# interconnexions.net
KiCad netlist of a schematic drawn in EAGLE
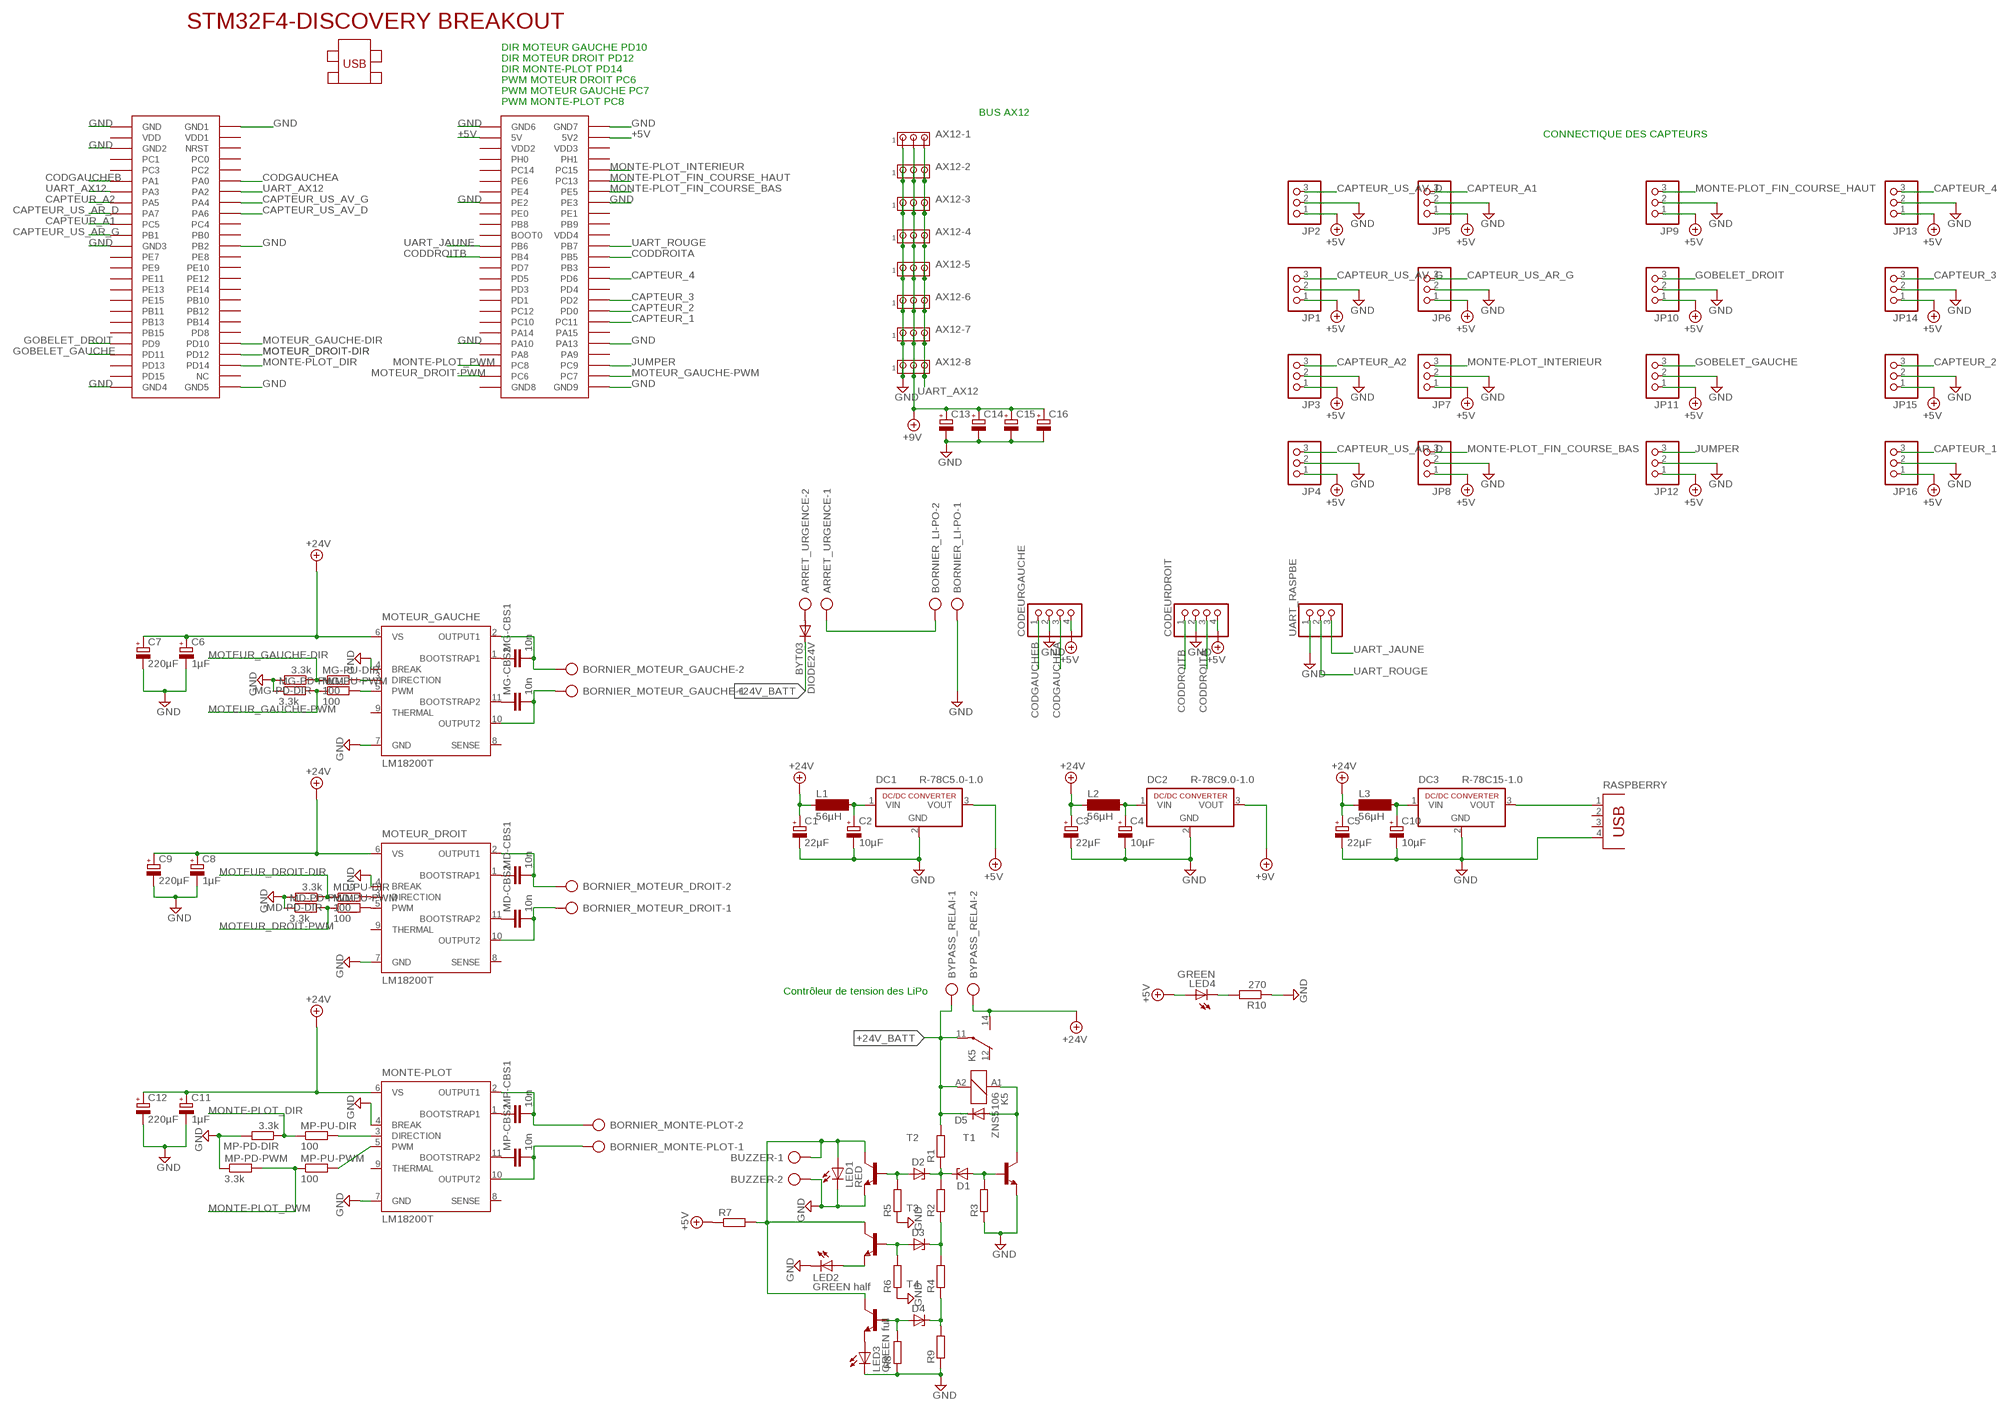
[diagram p0: schematic, sheet 1]

(export (version "E")
  (design (tool "Eeschema 10.0.6"))
  (components
    (comp (ref "ARRET_URGENCE")
      (value "AK300/2")
      (footprint "eagle-import:AK300_2")
      (libsource (lib "eagle-import") (part "AK300/2"))
    )
    (comp (ref "AX12-1")
      (value "MTA03-100")
      (footprint "eagle-import:10X03MTA")
      (libsource (lib "eagle-import") (part "MTA03-100"))
    )
    (comp (ref "AX12-2")
      (value "MTA03-100")
      (footprint "eagle-import:10X03MTA")
      (libsource (lib "eagle-import") (part "MTA03-100"))
    )
    (comp (ref "AX12-3")
      (value "MTA03-100")
      (footprint "eagle-import:10X03MTA")
      (libsource (lib "eagle-import") (part "MTA03-100"))
    )
    (comp (ref "AX12-4")
      (value "MTA03-100")
      (footprint "eagle-import:10X03MTA")
      (libsource (lib "eagle-import") (part "MTA03-100"))
    )
    (comp (ref "AX12-5")
      (value "MTA03-100")
      (footprint "eagle-import:10X03MTA")
      (libsource (lib "eagle-import") (part "MTA03-100"))
    )
    (comp (ref "AX12-6")
      (value "MTA03-100")
      (footprint "eagle-import:10X03MTA")
      (libsource (lib "eagle-import") (part "MTA03-100"))
    )
    (comp (ref "AX12-7")
      (value "MTA03-100")
      (footprint "eagle-import:10X03MTA")
      (libsource (lib "eagle-import") (part "MTA03-100"))
    )
    (comp (ref "AX12-8")
      (value "MTA03-100")
      (footprint "eagle-import:10X03MTA")
      (libsource (lib "eagle-import") (part "MTA03-100"))
    )
    (comp (ref "BORNIER_LI-PO")
      (value "AK300/2")
      (footprint "eagle-import:AK300_2")
      (libsource (lib "eagle-import") (part "AK300/2"))
    )
    (comp (ref "BORNIER_MONTE-PLOT")
      (value "AK300/2")
      (footprint "eagle-import:AK300_2")
      (libsource (lib "eagle-import") (part "AK300/2"))
    )
    (comp (ref "BORNIER_MOTEUR_DROIT")
      (value "AK300/2")
      (footprint "eagle-import:AK300_2")
      (libsource (lib "eagle-import") (part "AK300/2"))
    )
    (comp (ref "BORNIER_MOTEUR_GAUCHE")
      (value "AK300/2")
      (footprint "eagle-import:AK300_2")
      (libsource (lib "eagle-import") (part "AK300/2"))
    )
    (comp (ref "BUZZER")
      (value "AK300/2")
      (footprint "eagle-import:AK300_2")
      (libsource (lib "eagle-import") (part "AK300/2"))
    )
    (comp (ref "BYPASS_RELAI")
      (value "AK300/2")
      (footprint "eagle-import:AK300_2")
      (libsource (lib "eagle-import") (part "AK300/2"))
    )
    (comp (ref "C1")
      (value "22µF")
      (footprint "eagle-import:E2,5-6E")
      (libsource (lib "eagle-import") (part "resistor_CPOL-EUE2,5-6E"))
    )
    (comp (ref "C2")
      (value "10µF")
      (footprint "eagle-import:E2,5-6E")
      (libsource (lib "eagle-import") (part "resistor_CPOL-EUE2,5-6E"))
    )
    (comp (ref "C3")
      (value "22µF")
      (footprint "eagle-import:E2,5-6E")
      (libsource (lib "eagle-import") (part "resistor_CPOL-EUE2,5-6E"))
    )
    (comp (ref "C4")
      (value "10µF")
      (footprint "eagle-import:E2,5-6E")
      (libsource (lib "eagle-import") (part "resistor_CPOL-EUE2,5-6E"))
    )
    (comp (ref "C5")
      (value "22µF")
      (footprint "eagle-import:E2,5-6E")
      (libsource (lib "eagle-import") (part "resistor_CPOL-EUE2,5-6E"))
    )
    (comp (ref "C6")
      (value "1µF")
      (footprint "eagle-import:E3,5-8")
      (libsource (lib "eagle-import") (part "CPOL-EUE3.5-8"))
    )
    (comp (ref "C7")
      (value "220µF")
      (footprint "eagle-import:E3,5-8")
      (libsource (lib "eagle-import") (part "CPOL-EUE3.5-8"))
    )
    (comp (ref "C8")
      (value "1µF")
      (footprint "eagle-import:E3,5-8")
      (libsource (lib "eagle-import") (part "CPOL-EUE3.5-8"))
    )
    (comp (ref "C9")
      (value "220µF")
      (footprint "eagle-import:E3,5-8")
      (libsource (lib "eagle-import") (part "CPOL-EUE3.5-8"))
    )
    (comp (ref "C10")
      (value "10µF")
      (footprint "eagle-import:E2,5-6E")
      (libsource (lib "eagle-import") (part "resistor_CPOL-EUE2,5-6E"))
    )
    (comp (ref "C11")
      (value "1µF")
      (footprint "eagle-import:E3,5-8")
      (libsource (lib "eagle-import") (part "CPOL-EUE3.5-8"))
    )
    (comp (ref "C12")
      (value "220µF")
      (footprint "eagle-import:E3,5-8")
      (libsource (lib "eagle-import") (part "CPOL-EUE3.5-8"))
    )
    (comp (ref "C13")
      (value "CPOL-EUE2,5-6E")
      (footprint "eagle-import:E2,5-6E")
      (libsource (lib "eagle-import") (part "resistor_CPOL-EUE2,5-6E"))
    )
    (comp (ref "C14")
      (value "CPOL-EUE2,5-6E")
      (footprint "eagle-import:E2,5-6E")
      (libsource (lib "eagle-import") (part "resistor_CPOL-EUE2,5-6E"))
    )
    (comp (ref "C15")
      (value "CPOL-EUE2,5-6E")
      (footprint "eagle-import:E2,5-6E")
      (libsource (lib "eagle-import") (part "resistor_CPOL-EUE2,5-6E"))
    )
    (comp (ref "C16")
      (value "CPOL-EUE2,5-6E")
      (footprint "eagle-import:E2,5-6E")
      (libsource (lib "eagle-import") (part "resistor_CPOL-EUE2,5-6E"))
    )
    (comp (ref "CODEURDROIT")
      (value "PINHD-1X4")
      (footprint "eagle-import:1X04")
      (libsource (lib "eagle-import") (part "PINHD-1X4"))
    )
    (comp (ref "CODEURGAUCHE")
      (value "PINHD-1X4")
      (footprint "eagle-import:1X04")
      (libsource (lib "eagle-import") (part "PINHD-1X4"))
    )
    (comp (ref "D1")
      (value "ZENER-DIODEZD-2.5")
      (footprint "eagle-import:ZDIO-2.5")
      (libsource (lib "eagle-import") (part "ZENER-DIODEZD-2.5"))
    )
    (comp (ref "D2")
      (value "ZENER-DIODEZD-2.5")
      (footprint "eagle-import:ZDIO-2.5")
      (libsource (lib "eagle-import") (part "ZENER-DIODEZD-2.5"))
    )
    (comp (ref "D3")
      (value "ZENER-DIODEZD-2.5")
      (footprint "eagle-import:ZDIO-2.5")
      (libsource (lib "eagle-import") (part "ZENER-DIODEZD-2.5"))
    )
    (comp (ref "D4")
      (value "ZENER-DIODEZD-2.5")
      (footprint "eagle-import:ZDIO-2.5")
      (libsource (lib "eagle-import") (part "ZENER-DIODEZD-2.5"))
    )
    (comp (ref "D5")
      (value "DIODE-D-2.5")
      (footprint "eagle-import:D-2.5")
      (libsource (lib "eagle-import") (part "DIODE-D-2.5"))
    )
    (comp (ref "DC1")
      (value "R-78C5.0-1.0")
      (footprint "eagle-import:SIP3")
      (libsource (lib "eagle-import") (part "R-78C-1.05.0"))
    )
    (comp (ref "DC2")
      (value "R-78C9.0-1.0")
      (footprint "eagle-import:SIP3")
      (libsource (lib "eagle-import") (part "R-78C-1.09.0"))
    )
    (comp (ref "DC3")
      (value "R-78C15-1.0")
      (footprint "eagle-import:SIP3")
      (libsource (lib "eagle-import") (part "R-78C-1.015"))
    )
    (comp (ref "DIODE24V")
      (value "BYT03")
      (footprint "eagle-import:DO27-15")
      (libsource (lib "eagle-import") (part "BYT03"))
    )
    (comp (ref "JP1")
      (value "PINHD-1X3")
      (footprint "eagle-import:1X03")
      (libsource (lib "eagle-import") (part "PINHD-1X3"))
    )
    (comp (ref "JP2")
      (value "PINHD-1X3")
      (footprint "eagle-import:1X03")
      (libsource (lib "eagle-import") (part "PINHD-1X3"))
    )
    (comp (ref "JP3")
      (value "PINHD-1X3")
      (footprint "eagle-import:1X03")
      (libsource (lib "eagle-import") (part "PINHD-1X3"))
    )
    (comp (ref "JP4")
      (value "PINHD-1X3")
      (footprint "eagle-import:1X03")
      (libsource (lib "eagle-import") (part "PINHD-1X3"))
    )
    (comp (ref "JP5")
      (value "PINHD-1X3")
      (footprint "eagle-import:1X03")
      (libsource (lib "eagle-import") (part "PINHD-1X3"))
    )
    (comp (ref "JP6")
      (value "PINHD-1X3")
      (footprint "eagle-import:1X03")
      (libsource (lib "eagle-import") (part "PINHD-1X3"))
    )
    (comp (ref "JP7")
      (value "PINHD-1X3")
      (footprint "eagle-import:1X03")
      (libsource (lib "eagle-import") (part "PINHD-1X3"))
    )
    (comp (ref "JP8")
      (value "PINHD-1X3")
      (footprint "eagle-import:1X03")
      (libsource (lib "eagle-import") (part "PINHD-1X3"))
    )
    (comp (ref "JP9")
      (value "PINHD-1X3")
      (footprint "eagle-import:1X03")
      (libsource (lib "eagle-import") (part "PINHD-1X3"))
    )
    (comp (ref "JP10")
      (value "PINHD-1X3")
      (footprint "eagle-import:1X03")
      (libsource (lib "eagle-import") (part "PINHD-1X3"))
    )
    (comp (ref "JP11")
      (value "PINHD-1X3")
      (footprint "eagle-import:1X03")
      (libsource (lib "eagle-import") (part "PINHD-1X3"))
    )
    (comp (ref "JP12")
      (value "PINHD-1X3")
      (footprint "eagle-import:1X03")
      (libsource (lib "eagle-import") (part "PINHD-1X3"))
    )
    (comp (ref "JP13")
      (value "PINHD-1X3")
      (footprint "eagle-import:1X03")
      (libsource (lib "eagle-import") (part "PINHD-1X3"))
    )
    (comp (ref "JP14")
      (value "PINHD-1X3")
      (footprint "eagle-import:1X03")
      (libsource (lib "eagle-import") (part "PINHD-1X3"))
    )
    (comp (ref "JP15")
      (value "PINHD-1X3")
      (footprint "eagle-import:1X03")
      (libsource (lib "eagle-import") (part "PINHD-1X3"))
    )
    (comp (ref "JP16")
      (value "PINHD-1X3")
      (footprint "eagle-import:1X03")
      (libsource (lib "eagle-import") (part "PINHD-1X3"))
    )
    (comp (ref "K5")
      (value "ZNS5106")
      (footprint "eagle-import:ZN5")
      (libsource (lib "eagle-import") (part "ZNS5106"))
    )
    (comp (ref "L1")
      (value "56µH")
      (footprint "eagle-import:SD12K100")
      (libsource (lib "eagle-import") (part "SD12K100"))
    )
    (comp (ref "L2")
      (value "56µH")
      (footprint "eagle-import:SD12K100")
      (libsource (lib "eagle-import") (part "SD12K100"))
    )
    (comp (ref "L3")
      (value "56µH")
      (footprint "eagle-import:SD12K100")
      (libsource (lib "eagle-import") (part "SD12K100"))
    )
    (comp (ref "LED1")
      (value "RED")
      (footprint "eagle-import:LED5MM")
      (libsource (lib "eagle-import") (part "LED5MM"))
    )
    (comp (ref "LED2")
      (value "GREEN half")
      (footprint "eagle-import:LED5MM")
      (libsource (lib "eagle-import") (part "LED5MM"))
    )
    (comp (ref "LED3")
      (value "GREEN full")
      (footprint "eagle-import:LED5MM")
      (libsource (lib "eagle-import") (part "LED5MM"))
    )
    (comp (ref "LED4")
      (value "GREEN")
      (footprint "eagle-import:LED5MM")
      (libsource (lib "eagle-import") (part "LED5MM"))
    )
    (comp (ref "MD-CBS1")
      (value "10n")
      (footprint "eagle-import:C050-025X075")
      (libsource (lib "eagle-import") (part "C-EU050-025X075"))
    )
    (comp (ref "MD-CBS2")
      (value "10n")
      (footprint "eagle-import:C050-025X075")
      (libsource (lib "eagle-import") (part "C-EU050-025X075"))
    )
    (comp (ref "MD-PD-DIR")
      (value "3.3k")
      (footprint "eagle-import:0207_10")
      (libsource (lib "eagle-import") (part "R-EU_0207/10"))
    )
    (comp (ref "MD-PD-PWM")
      (value "3.3k")
      (footprint "eagle-import:0207_7")
      (libsource (lib "eagle-import") (part "resistor_R-EU_0207/7"))
    )
    (comp (ref "MD-PU-DIR")
      (value "100")
      (footprint "eagle-import:0207_7")
      (libsource (lib "eagle-import") (part "R-EU_0207/7"))
    )
    (comp (ref "MD-PU-PWM")
      (value "100")
      (footprint "eagle-import:0207_15")
      (libsource (lib "eagle-import") (part "resistor_R-EU_0207/15"))
    )
    (comp (ref "MG-CBS1")
      (value "10n")
      (footprint "eagle-import:C050-025X075")
      (libsource (lib "eagle-import") (part "C-EU050-025X075"))
    )
    (comp (ref "MG-CBS2")
      (value "10n")
      (footprint "eagle-import:C050-025X075")
      (libsource (lib "eagle-import") (part "C-EU050-025X075"))
    )
    (comp (ref "MG-PD-DIR")
      (value "3.3k")
      (footprint "eagle-import:0207_7")
      (libsource (lib "eagle-import") (part "R-EU_0207/7"))
    )
    (comp (ref "MG-PD-PWM")
      (value "3.3k")
      (footprint "eagle-import:0207_7")
      (libsource (lib "eagle-import") (part "resistor_R-EU_0207/7"))
    )
    (comp (ref "MG-PU-DIR")
      (value "100")
      (footprint "eagle-import:0207_7")
      (libsource (lib "eagle-import") (part "R-EU_0207/7"))
    )
    (comp (ref "MG-PU-PWM")
      (value "100")
      (footprint "eagle-import:0207_15")
      (libsource (lib "eagle-import") (part "resistor_R-EU_0207/15"))
    )
    (comp (ref "MONTE-PLOT")
      (value "LM18200T")
      (footprint "eagle-import:TO-220-11")
      (libsource (lib "eagle-import") (part "LM18200T"))
    )
    (comp (ref "MOTEUR_DROIT")
      (value "LM18200T")
      (footprint "eagle-import:TO-220-11")
      (libsource (lib "eagle-import") (part "LM18200T"))
    )
    (comp (ref "MOTEUR_GAUCHE")
      (value "LM18200T")
      (footprint "eagle-import:TO-220-11")
      (libsource (lib "eagle-import") (part "LM18200T"))
    )
    (comp (ref "MP-CBS1")
      (value "10n")
      (footprint "eagle-import:C050-025X075")
      (libsource (lib "eagle-import") (part "C-EU050-025X075"))
    )
    (comp (ref "MP-CBS2")
      (value "10n")
      (footprint "eagle-import:C050-025X075")
      (libsource (lib "eagle-import") (part "C-EU050-025X075"))
    )
    (comp (ref "MP-PD-DIR")
      (value "3.3k")
      (footprint "eagle-import:0207_10")
      (libsource (lib "eagle-import") (part "R-EU_0207/10"))
    )
    (comp (ref "MP-PD-PWM")
      (value "3.3k")
      (footprint "eagle-import:0207_7")
      (libsource (lib "eagle-import") (part "resistor_R-EU_0207/7"))
    )
    (comp (ref "MP-PU-DIR")
      (value "100")
      (footprint "eagle-import:0207_7")
      (libsource (lib "eagle-import") (part "R-EU_0207/7"))
    )
    (comp (ref "MP-PU-PWM")
      (value "100")
      (footprint "eagle-import:0207_15")
      (libsource (lib "eagle-import") (part "resistor_R-EU_0207/15"))
    )
    (comp (ref "R1")
      (value "R-EU_0207/2V")
      (footprint "eagle-import:0207_2V")
      (libsource (lib "eagle-import") (part "R-EU_0207/2V"))
    )
    (comp (ref "R2")
      (value "R-EU_0204/7")
      (footprint "eagle-import:0204_7")
      (libsource (lib "eagle-import") (part "resistor_R-EU_0204/7"))
    )
    (comp (ref "R3")
      (value "R-EU_0207/2V")
      (footprint "eagle-import:0207_2V")
      (libsource (lib "eagle-import") (part "resistor_R-EU_0207/2V"))
    )
    (comp (ref "R4")
      (value "R-EU_0204/7")
      (footprint "eagle-import:0204_7")
      (libsource (lib "eagle-import") (part "resistor_R-EU_0204/7"))
    )
    (comp (ref "R5")
      (value "R-EU_0207/2V")
      (footprint "eagle-import:0207_2V")
      (libsource (lib "eagle-import") (part "resistor_R-EU_0207/2V"))
    )
    (comp (ref "R6")
      (value "R-EU_0207/2V")
      (footprint "eagle-import:0207_2V")
      (libsource (lib "eagle-import") (part "resistor_R-EU_0207/2V"))
    )
    (comp (ref "R7")
      (value "R-EU_0204/7")
      (footprint "eagle-import:0204_7")
      (libsource (lib "eagle-import") (part "resistor_R-EU_0204/7"))
    )
    (comp (ref "R8")
      (value "R-EU_0204/5")
      (footprint "eagle-import:0204_5")
      (libsource (lib "eagle-import") (part "R-EU_0204/5"))
    )
    (comp (ref "R9")
      (value "R-EU_0204/7")
      (footprint "eagle-import:0204_7")
      (libsource (lib "eagle-import") (part "resistor_R-EU_0204/7"))
    )
    (comp (ref "R10")
      (value "270")
      (footprint "eagle-import:0207_2V")
      (libsource (lib "eagle-import") (part "R-EU_0207/2V"))
    )
    (comp (ref "RASPBERRY")
      (value "PN87520")
      (footprint "eagle-import:PN87520")
      (libsource (lib "eagle-import") (part "PN87520"))
    )
    (comp (ref "T1")
      (value "2N5400-NPN-TO92-CBE")
      (footprint "eagle-import:TO92-CBE")
      (libsource (lib "eagle-import") (part "-NPN-TO92-CBE2N5400"))
    )
    (comp (ref "T2")
      (value "2N5400-NPN-TO92-CBE")
      (footprint "eagle-import:TO92-CBE")
      (libsource (lib "eagle-import") (part "-NPN-TO92-CBE2N5400"))
    )
    (comp (ref "T3")
      (value "2N5400-NPN-TO92-CBE")
      (footprint "eagle-import:TO92-CBE")
      (libsource (lib "eagle-import") (part "-NPN-TO92-CBE2N5400"))
    )
    (comp (ref "T4")
      (value "2N5400-NPN-TO92-CBE")
      (footprint "eagle-import:TO92-CBE")
      (libsource (lib "eagle-import") (part "-NPN-TO92-CBE2N5400"))
    )
    (comp (ref "U$1")
      (value "STM32F4-DISCOVERY")
      (footprint "eagle-import:STM32F4-DISCOVERY")
      (libsource (lib "eagle-import") (part "STM32F4-DISCOVERY"))
    )
    (comp (ref "UART_RASPBE")
      (value "PINHD-1X3")
      (footprint "eagle-import:1X03")
      (libsource (lib "eagle-import") (part "PINHD-1X3"))
    )
  )
  (nets
    (net (code "1") (name "+5V") (class "Default")
      (node (ref "CODEURDROIT") (pin "4") (pinfunction "4_4") (pintype "passive"))
      (node (ref "CODEURGAUCHE") (pin "4") (pinfunction "4_4") (pintype "passive"))
      (node (ref "DC1") (pin "3") (pinfunction "VOUT_3") (pintype "passive"))
      (node (ref "JP1") (pin "1") (pinfunction "1_1") (pintype "passive"))
      (node (ref "JP10") (pin "1") (pinfunction "1_1") (pintype "passive"))
      (node (ref "JP11") (pin "1") (pinfunction "1_1") (pintype "passive"))
      (node (ref "JP12") (pin "1") (pinfunction "1_1") (pintype "passive"))
      (node (ref "JP13") (pin "1") (pinfunction "1_1") (pintype "passive"))
      (node (ref "JP14") (pin "1") (pinfunction "1_1") (pintype "passive"))
      (node (ref "JP15") (pin "1") (pinfunction "1_1") (pintype "passive"))
      (node (ref "JP16") (pin "1") (pinfunction "1_1") (pintype "passive"))
      (node (ref "JP2") (pin "1") (pinfunction "1_1") (pintype "passive"))
      (node (ref "JP3") (pin "1") (pinfunction "1_1") (pintype "passive"))
      (node (ref "JP4") (pin "1") (pinfunction "1_1") (pintype "passive"))
      (node (ref "JP5") (pin "1") (pinfunction "1_1") (pintype "passive"))
      (node (ref "JP6") (pin "1") (pinfunction "1_1") (pintype "passive"))
      (node (ref "JP7") (pin "1") (pinfunction "1_1") (pintype "passive"))
      (node (ref "JP8") (pin "1") (pinfunction "1_1") (pintype "passive"))
      (node (ref "JP9") (pin "1") (pinfunction "1_1") (pintype "passive"))
      (node (ref "LED4") (pin "A") (pinfunction "A_A") (pintype "passive"))
      (node (ref "R7") (pin "1") (pinfunction "1_1") (pintype "passive"))
      (node (ref "U$1") (pin "P$53") (pinfunction "5V_P$53") (pintype "bidirectional"))
      (node (ref "U$1") (pin "P$54") (pinfunction "5V2_P$54") (pintype "bidirectional"))
    )
    (net (code "2") (name "+9V") (class "Default")
      (node (ref "AX12-1") (pin "2") (pinfunction "2_2") (pintype "passive"))
      (node (ref "AX12-2") (pin "2") (pinfunction "2_2") (pintype "passive"))
      (node (ref "AX12-3") (pin "2") (pinfunction "2_2") (pintype "passive"))
      (node (ref "AX12-4") (pin "2") (pinfunction "2_2") (pintype "passive"))
      (node (ref "AX12-5") (pin "2") (pinfunction "2_2") (pintype "passive"))
      (node (ref "AX12-6") (pin "2") (pinfunction "2_2") (pintype "passive"))
      (node (ref "AX12-7") (pin "2") (pinfunction "2_2") (pintype "passive"))
      (node (ref "AX12-8") (pin "2") (pinfunction "2_2") (pintype "passive"))
      (node (ref "C13") (pin "+") (pinfunction "+_+") (pintype "passive"))
      (node (ref "C14") (pin "+") (pinfunction "+_+") (pintype "passive"))
      (node (ref "C15") (pin "+") (pinfunction "+_+") (pintype "passive"))
      (node (ref "C16") (pin "+") (pinfunction "+_+") (pintype "passive"))
      (node (ref "DC2") (pin "3") (pinfunction "VOUT_3") (pintype "passive"))
    )
    (net (code "3") (name "+24V") (class "Default")
      (node (ref "BYPASS_RELAI") (pin "2") (pinfunction "KL_2") (pintype "passive"))
      (node (ref "C1") (pin "+") (pinfunction "+_+") (pintype "passive"))
      (node (ref "C11") (pin "+") (pinfunction "+_+") (pintype "passive"))
      (node (ref "C12") (pin "+") (pinfunction "+_+") (pintype "passive"))
      (node (ref "C3") (pin "+") (pinfunction "+_+") (pintype "passive"))
      (node (ref "C5") (pin "+") (pinfunction "+_+") (pintype "passive"))
      (node (ref "C6") (pin "+") (pinfunction "+_+") (pintype "passive"))
      (node (ref "C7") (pin "+") (pinfunction "+_+") (pintype "passive"))
      (node (ref "C8") (pin "+") (pinfunction "+_+") (pintype "passive"))
      (node (ref "C9") (pin "+") (pinfunction "+_+") (pintype "passive"))
      (node (ref "K5") (pin "14") (pinfunction "S_14") (pintype "passive"))
      (node (ref "L1") (pin "1") (pinfunction "1_1") (pintype "passive"))
      (node (ref "L2") (pin "1") (pinfunction "1_1") (pintype "passive"))
      (node (ref "L3") (pin "1") (pinfunction "1_1") (pintype "passive"))
      (node (ref "MONTE-PLOT") (pin "6") (pinfunction "VS_6") (pintype "power_in"))
      (node (ref "MOTEUR_DROIT") (pin "6") (pinfunction "VS_6") (pintype "power_in"))
      (node (ref "MOTEUR_GAUCHE") (pin "6") (pinfunction "VS_6") (pintype "power_in"))
    )
    (net (code "4") (name "+24V_BATT") (class "Default")
      (node (ref "BYPASS_RELAI") (pin "1") (pinfunction "KL_1") (pintype "passive"))
      (node (ref "D5") (pin "C") (pinfunction "C_C") (pintype "passive"))
      (node (ref "DIODE24V") (pin "C") (pinfunction "C_C") (pintype "passive"))
      (node (ref "K5") (pin "11") (pinfunction "P_11") (pintype "passive"))
      (node (ref "K5") (pin "A2") (pinfunction "2_A2") (pintype "passive"))
      (node (ref "R1") (pin "2") (pinfunction "2_2") (pintype "passive"))
    )
    (net (code "5") (name "/CAPTEUR_1") (class "Default")
      (node (ref "JP16") (pin "3") (pinfunction "3_3") (pintype "passive"))
      (node (ref "U$1") (pin "P$88") (pinfunction "PC11_P$88") (pintype "bidirectional"))
    )
    (net (code "6") (name "/CAPTEUR_2") (class "Default")
      (node (ref "JP15") (pin "3") (pinfunction "3_3") (pintype "passive"))
      (node (ref "U$1") (pin "P$86") (pinfunction "PD0_P$86") (pintype "bidirectional"))
    )
    (net (code "7") (name "/CAPTEUR_3") (class "Default")
      (node (ref "JP14") (pin "3") (pinfunction "3_3") (pintype "passive"))
      (node (ref "U$1") (pin "P$84") (pinfunction "PD2_P$84") (pintype "bidirectional"))
    )
    (net (code "8") (name "/CAPTEUR_4") (class "Default")
      (node (ref "JP13") (pin "3") (pinfunction "3_3") (pintype "passive"))
      (node (ref "U$1") (pin "P$80") (pinfunction "PD6_P$80") (pintype "bidirectional"))
    )
    (net (code "9") (name "/CAPTEUR_A1") (class "Default")
      (node (ref "JP5") (pin "3") (pinfunction "3_3") (pintype "passive"))
      (node (ref "U$1") (pin "P$19") (pinfunction "PC5_P$19") (pintype "bidirectional"))
    )
    (net (code "10") (name "/CAPTEUR_A2") (class "Default")
      (node (ref "JP3") (pin "3") (pinfunction "3_3") (pintype "passive"))
      (node (ref "U$1") (pin "P$15") (pinfunction "PA5_P$15") (pintype "bidirectional"))
    )
    (net (code "11") (name "/CAPTEUR_US_AR_D") (class "Default")
      (node (ref "JP4") (pin "3") (pinfunction "3_3") (pintype "passive"))
      (node (ref "U$1") (pin "P$17") (pinfunction "PA7_P$17") (pintype "bidirectional"))
    )
    (net (code "12") (name "/CAPTEUR_US_AR_G") (class "Default")
      (node (ref "JP6") (pin "3") (pinfunction "3_3") (pintype "passive"))
      (node (ref "U$1") (pin "P$21") (pinfunction "PB1_P$21") (pintype "bidirectional"))
    )
    (net (code "13") (name "/CAPTEUR_US_AV_D") (class "Default")
      (node (ref "JP2") (pin "3") (pinfunction "3_3") (pintype "passive"))
      (node (ref "U$1") (pin "P$18") (pinfunction "PA6_P$18") (pintype "bidirectional"))
    )
    (net (code "14") (name "/CAPTEUR_US_AV_G") (class "Default")
      (node (ref "JP1") (pin "3") (pinfunction "3_3") (pintype "passive"))
      (node (ref "U$1") (pin "P$16") (pinfunction "PA4_P$16") (pintype "bidirectional"))
    )
    (net (code "15") (name "/CODDROITA") (class "Default")
      (node (ref "CODEURDROIT") (pin "3") (pinfunction "3_3") (pintype "passive"))
      (node (ref "U$1") (pin "P$76") (pinfunction "PB5_P$76") (pintype "bidirectional"))
    )
    (net (code "16") (name "/CODDROITB") (class "Default")
      (node (ref "CODEURDROIT") (pin "1") (pinfunction "1_1") (pintype "passive"))
      (node (ref "U$1") (pin "P$75") (pinfunction "PB4_P$75") (pintype "bidirectional"))
    )
    (net (code "17") (name "/CODGAUCHEA") (class "Default")
      (node (ref "CODEURGAUCHE") (pin "3") (pinfunction "3_3") (pintype "passive"))
      (node (ref "U$1") (pin "P$12") (pinfunction "PA0_P$12") (pintype "bidirectional"))
    )
    (net (code "18") (name "/CODGAUCHEB") (class "Default")
      (node (ref "CODEURGAUCHE") (pin "1") (pinfunction "1_1") (pintype "passive"))
      (node (ref "U$1") (pin "P$11") (pinfunction "PA1_P$11") (pintype "bidirectional"))
    )
    (net (code "19") (name "/GOBELET_DROIT") (class "Default")
      (node (ref "JP10") (pin "3") (pinfunction "3_3") (pintype "passive"))
      (node (ref "U$1") (pin "P$41") (pinfunction "PD9_P$41") (pintype "bidirectional"))
    )
    (net (code "20") (name "/GOBELET_GAUCHE") (class "Default")
      (node (ref "JP11") (pin "3") (pinfunction "3_3") (pintype "passive"))
      (node (ref "U$1") (pin "P$43") (pinfunction "PD11_P$43") (pintype "bidirectional"))
    )
    (net (code "21") (name "/JUMPER") (class "Default")
      (node (ref "JP12") (pin "3") (pinfunction "3_3") (pintype "passive"))
      (node (ref "U$1") (pin "P$96") (pinfunction "PC9_P$96") (pintype "bidirectional"))
    )
    (net (code "22") (name "/MONTE-PLOT_DIR") (class "Default")
      (node (ref "MP-PD-DIR") (pin "1") (pinfunction "1_1") (pintype "passive"))
      (node (ref "MP-PU-DIR") (pin "1") (pinfunction "1_1") (pintype "passive"))
      (node (ref "U$1") (pin "P$46") (pinfunction "PD14_P$46") (pintype "bidirectional"))
    )
    (net (code "23") (name "/MONTE-PLOT_FIN_COURSE_BAS") (class "Default")
      (node (ref "JP8") (pin "3") (pinfunction "3_3") (pintype "passive"))
      (node (ref "U$1") (pin "P$64") (pinfunction "PE5_P$64") (pintype "bidirectional"))
    )
    (net (code "24") (name "/MONTE-PLOT_FIN_COURSE_HAUT") (class "Default")
      (node (ref "JP9") (pin "3") (pinfunction "3_3") (pintype "passive"))
      (node (ref "U$1") (pin "P$62") (pinfunction "PC13_P$62") (pintype "bidirectional"))
    )
    (net (code "25") (name "/MONTE-PLOT_INTERIEUR") (class "Default")
      (node (ref "JP7") (pin "3") (pinfunction "3_3") (pintype "passive"))
      (node (ref "U$1") (pin "P$60") (pinfunction "PC15_P$60") (pintype "bidirectional"))
    )
    (net (code "26") (name "/MONTE-PLOT_PWM") (class "Default")
      (node (ref "MP-PD-PWM") (pin "2") (pinfunction "2_2") (pintype "passive"))
      (node (ref "MP-PU-PWM") (pin "1") (pinfunction "1_1") (pintype "passive"))
      (node (ref "U$1") (pin "P$95") (pinfunction "PC8_P$95") (pintype "bidirectional"))
    )
    (net (code "27") (name "/MOTEUR_DROIT-DIR") (class "Default")
      (node (ref "MD-PD-DIR") (pin "1") (pinfunction "1_1") (pintype "passive"))
      (node (ref "MD-PU-DIR") (pin "1") (pinfunction "1_1") (pintype "passive"))
      (node (ref "U$1") (pin "P$44") (pinfunction "PD12_P$44") (pintype "bidirectional"))
    )
    (net (code "28") (name "/MOTEUR_DROIT-PWM") (class "Default")
      (node (ref "MD-PD-PWM") (pin "2") (pinfunction "2_2") (pintype "passive"))
      (node (ref "MD-PU-PWM") (pin "1") (pinfunction "1_1") (pintype "passive"))
      (node (ref "U$1") (pin "P$97") (pinfunction "PC6_P$97") (pintype "bidirectional"))
    )
    (net (code "29") (name "/MOTEUR_GAUCHE-DIR") (class "Default")
      (node (ref "MG-PD-DIR") (pin "1") (pinfunction "1_1") (pintype "passive"))
      (node (ref "MG-PU-DIR") (pin "1") (pinfunction "1_1") (pintype "passive"))
      (node (ref "U$1") (pin "P$42") (pinfunction "PD10_P$42") (pintype "bidirectional"))
    )
    (net (code "30") (name "/MOTEUR_GAUCHE-PWM") (class "Default")
      (node (ref "MG-PD-PWM") (pin "2") (pinfunction "2_2") (pintype "passive"))
      (node (ref "MG-PU-PWM") (pin "1") (pinfunction "1_1") (pintype "passive"))
      (node (ref "U$1") (pin "P$98") (pinfunction "PC7_P$98") (pintype "bidirectional"))
    )
    (net (code "31") (name "/UART_AX12") (class "Default")
      (node (ref "AX12-1") (pin "3") (pinfunction "3_3") (pintype "passive"))
      (node (ref "AX12-2") (pin "3") (pinfunction "3_3") (pintype "passive"))
      (node (ref "AX12-3") (pin "3") (pinfunction "3_3") (pintype "passive"))
      (node (ref "AX12-4") (pin "3") (pinfunction "3_3") (pintype "passive"))
      (node (ref "AX12-5") (pin "3") (pinfunction "3_3") (pintype "passive"))
      (node (ref "AX12-6") (pin "3") (pinfunction "3_3") (pintype "passive"))
      (node (ref "AX12-7") (pin "3") (pinfunction "3_3") (pintype "passive"))
      (node (ref "AX12-8") (pin "3") (pinfunction "3_3") (pintype "passive"))
      (node (ref "U$1") (pin "P$13") (pinfunction "PA3_P$13") (pintype "bidirectional"))
      (node (ref "U$1") (pin "P$14") (pinfunction "PA2_P$14") (pintype "bidirectional"))
    )
    (net (code "32") (name "/UART_JAUNE") (class "Default")
      (node (ref "U$1") (pin "P$73") (pinfunction "PB6_P$73") (pintype "bidirectional"))
      (node (ref "UART_RASPBE") (pin "3") (pinfunction "3_3") (pintype "passive"))
    )
    (net (code "33") (name "/UART_ROUGE") (class "Default")
      (node (ref "U$1") (pin "P$74") (pinfunction "PB7_P$74") (pintype "bidirectional"))
      (node (ref "UART_RASPBE") (pin "2") (pinfunction "2_2") (pintype "passive"))
    )
    (net (code "34") (name "GND") (class "Default")
      (node (ref "AX12-1") (pin "1") (pinfunction "1_1") (pintype "passive"))
      (node (ref "AX12-2") (pin "1") (pinfunction "1_1") (pintype "passive"))
      (node (ref "AX12-3") (pin "1") (pinfunction "1_1") (pintype "passive"))
      (node (ref "AX12-4") (pin "1") (pinfunction "1_1") (pintype "passive"))
      (node (ref "AX12-5") (pin "1") (pinfunction "1_1") (pintype "passive"))
      (node (ref "AX12-6") (pin "1") (pinfunction "1_1") (pintype "passive"))
      (node (ref "AX12-7") (pin "1") (pinfunction "1_1") (pintype "passive"))
      (node (ref "AX12-8") (pin "1") (pinfunction "1_1") (pintype "passive"))
      (node (ref "BORNIER_LI-PO") (pin "1") (pinfunction "KL_1") (pintype "passive"))
      (node (ref "BUZZER") (pin "2") (pinfunction "KL_2") (pintype "passive"))
      (node (ref "C1") (pin "-") (pinfunction "-_-") (pintype "passive"))
      (node (ref "C10") (pin "-") (pinfunction "-_-") (pintype "passive"))
      (node (ref "C11") (pin "-") (pinfunction "-_-") (pintype "passive"))
      (node (ref "C12") (pin "-") (pinfunction "-_-") (pintype "passive"))
      (node (ref "C13") (pin "-") (pinfunction "-_-") (pintype "passive"))
      (node (ref "C14") (pin "-") (pinfunction "-_-") (pintype "passive"))
      (node (ref "C15") (pin "-") (pinfunction "-_-") (pintype "passive"))
      (node (ref "C16") (pin "-") (pinfunction "-_-") (pintype "passive"))
      (node (ref "C2") (pin "-") (pinfunction "-_-") (pintype "passive"))
      (node (ref "C3") (pin "-") (pinfunction "-_-") (pintype "passive"))
      (node (ref "C4") (pin "-") (pinfunction "-_-") (pintype "passive"))
      (node (ref "C5") (pin "-") (pinfunction "-_-") (pintype "passive"))
      (node (ref "C6") (pin "-") (pinfunction "-_-") (pintype "passive"))
      (node (ref "C7") (pin "-") (pinfunction "-_-") (pintype "passive"))
      (node (ref "C8") (pin "-") (pinfunction "-_-") (pintype "passive"))
      (node (ref "C9") (pin "-") (pinfunction "-_-") (pintype "passive"))
      (node (ref "CODEURDROIT") (pin "2") (pinfunction "2_2") (pintype "passive"))
      (node (ref "CODEURGAUCHE") (pin "2") (pinfunction "2_2") (pintype "passive"))
      (node (ref "DC1") (pin "2") (pinfunction "GND_2") (pintype "passive"))
      (node (ref "DC2") (pin "2") (pinfunction "GND_2") (pintype "passive"))
      (node (ref "DC3") (pin "2") (pinfunction "GND_2") (pintype "passive"))
      (node (ref "JP1") (pin "2") (pinfunction "2_2") (pintype "passive"))
      (node (ref "JP10") (pin "2") (pinfunction "2_2") (pintype "passive"))
      (node (ref "JP11") (pin "2") (pinfunction "2_2") (pintype "passive"))
      (node (ref "JP12") (pin "2") (pinfunction "2_2") (pintype "passive"))
      (node (ref "JP13") (pin "2") (pinfunction "2_2") (pintype "passive"))
      (node (ref "JP14") (pin "2") (pinfunction "2_2") (pintype "passive"))
      (node (ref "JP15") (pin "2") (pinfunction "2_2") (pintype "passive"))
      (node (ref "JP16") (pin "2") (pinfunction "2_2") (pintype "passive"))
      (node (ref "JP2") (pin "2") (pinfunction "2_2") (pintype "passive"))
      (node (ref "JP3") (pin "2") (pinfunction "2_2") (pintype "passive"))
      (node (ref "JP4") (pin "2") (pinfunction "2_2") (pintype "passive"))
      (node (ref "JP5") (pin "2") (pinfunction "2_2") (pintype "passive"))
      (node (ref "JP6") (pin "2") (pinfunction "2_2") (pintype "passive"))
      (node (ref "JP7") (pin "2") (pinfunction "2_2") (pintype "passive"))
      (node (ref "JP8") (pin "2") (pinfunction "2_2") (pintype "passive"))
      (node (ref "JP9") (pin "2") (pinfunction "2_2") (pintype "passive"))
      (node (ref "LED1") (pin "K") (pinfunction "C_K") (pintype "passive"))
      (node (ref "LED2") (pin "K") (pinfunction "C_K") (pintype "passive"))
      (node (ref "LED3") (pin "K") (pinfunction "C_K") (pintype "passive"))
      (node (ref "MD-PD-DIR") (pin "2") (pinfunction "2_2") (pintype "passive"))
      (node (ref "MD-PD-PWM") (pin "1") (pinfunction "1_1") (pintype "passive"))
      (node (ref "MG-PD-DIR") (pin "2") (pinfunction "2_2") (pintype "passive"))
      (node (ref "MG-PD-PWM") (pin "1") (pinfunction "1_1") (pintype "passive"))
      (node (ref "MONTE-PLOT") (pin "4") (pinfunction "BREAK_4") (pintype "input"))
      (node (ref "MONTE-PLOT") (pin "7") (pinfunction "GND_7") (pintype "power_in"))
      (node (ref "MOTEUR_DROIT") (pin "4") (pinfunction "BREAK_4") (pintype "input"))
      (node (ref "MOTEUR_DROIT") (pin "7") (pinfunction "GND_7") (pintype "power_in"))
      (node (ref "MOTEUR_GAUCHE") (pin "4") (pinfunction "BREAK_4") (pintype "input"))
      (node (ref "MOTEUR_GAUCHE") (pin "7") (pinfunction "GND_7") (pintype "power_in"))
      (node (ref "MP-PD-DIR") (pin "2") (pinfunction "2_2") (pintype "passive"))
      (node (ref "MP-PD-PWM") (pin "1") (pinfunction "1_1") (pintype "passive"))
      (node (ref "R10") (pin "1") (pinfunction "1_1") (pintype "passive"))
      (node (ref "R3") (pin "1") (pinfunction "1_1") (pintype "passive"))
      (node (ref "R5") (pin "1") (pinfunction "1_1") (pintype "passive"))
      (node (ref "R6") (pin "1") (pinfunction "1_1") (pintype "passive"))
      (node (ref "R8") (pin "1") (pinfunction "1_1") (pintype "passive"))
      (node (ref "R9") (pin "1") (pinfunction "1_1") (pintype "passive"))
      (node (ref "RASPBERRY") (pin "4") (pinfunction "4_4") (pintype "passive"))
      (node (ref "T1") (pin "E") (pinfunction "E_E") (pintype "passive"))
      (node (ref "T2") (pin "E") (pinfunction "E_E") (pintype "passive"))
      (node (ref "U$1") (pin "P$1") (pinfunction "GND_P$1") (pintype "bidirectional"))
      (node (ref "U$1") (pin "P$100") (pinfunction "GND9_P$100") (pintype "bidirectional"))
      (node (ref "U$1") (pin "P$2") (pinfunction "GND1_P$2") (pintype "bidirectional"))
      (node (ref "U$1") (pin "P$23") (pinfunction "GND3_P$23") (pintype "bidirectional"))
      (node (ref "U$1") (pin "P$24") (pinfunction "PB2_P$24") (pintype "bidirectional"))
      (node (ref "U$1") (pin "P$49") (pinfunction "GND4_P$49") (pintype "bidirectional"))
      (node (ref "U$1") (pin "P$5") (pinfunction "GND2_P$5") (pintype "bidirectional"))
      (node (ref "U$1") (pin "P$50") (pinfunction "GND5_P$50") (pintype "bidirectional"))
      (node (ref "U$1") (pin "P$51") (pinfunction "GND6_P$51") (pintype "bidirectional"))
      (node (ref "U$1") (pin "P$52") (pinfunction "GND7_P$52") (pintype "bidirectional"))
      (node (ref "U$1") (pin "P$65") (pinfunction "PE2_P$65") (pintype "bidirectional"))
      (node (ref "U$1") (pin "P$66") (pinfunction "PE3_P$66") (pintype "bidirectional"))
      (node (ref "U$1") (pin "P$91") (pinfunction "PA10_P$91") (pintype "bidirectional"))
      (node (ref "U$1") (pin "P$92") (pinfunction "PA13_P$92") (pintype "bidirectional"))
      (node (ref "UART_RASPBE") (pin "1") (pinfunction "1_1") (pintype "passive"))
    )
    (net (code "35") (name "Net-(ARRET_URGENCEA-KL)") (class "Default")
      (node (ref "ARRET_URGENCE") (pin "1") (pinfunction "KL_1") (pintype "passive"))
      (node (ref "BORNIER_LI-PO") (pin "2") (pinfunction "KL_2") (pintype "passive"))
    )
    (net (code "36") (name "Net-(ARRET_URGENCEB-KL)") (class "Default")
      (node (ref "ARRET_URGENCE") (pin "2") (pinfunction "KL_2") (pintype "passive"))
      (node (ref "DIODE24V") (pin "A") (pinfunction "A_A") (pintype "passive"))
    )
    (net (code "37") (name "Net-(BORNIER_MONTE-PLOTA-KL)") (class "Default")
      (node (ref "BORNIER_MONTE-PLOT") (pin "1") (pinfunction "KL_1") (pintype "passive"))
      (node (ref "MONTE-PLOT") (pin "10") (pinfunction "OUTPUT2_10") (pintype "output"))
      (node (ref "MP-CBS2") (pin "2") (pinfunction "2_2") (pintype "passive"))
    )
    (net (code "38") (name "Net-(BORNIER_MONTE-PLOTB-KL)") (class "Default")
      (node (ref "BORNIER_MONTE-PLOT") (pin "2") (pinfunction "KL_2") (pintype "passive"))
      (node (ref "MONTE-PLOT") (pin "2") (pinfunction "OUTPUT1_2") (pintype "output"))
      (node (ref "MP-CBS1") (pin "2") (pinfunction "2_2") (pintype "passive"))
    )
    (net (code "39") (name "Net-(BORNIER_MOTEUR_DROITA-KL)") (class "Default")
      (node (ref "BORNIER_MOTEUR_DROIT") (pin "1") (pinfunction "KL_1") (pintype "passive"))
      (node (ref "MD-CBS2") (pin "2") (pinfunction "2_2") (pintype "passive"))
      (node (ref "MOTEUR_DROIT") (pin "10") (pinfunction "OUTPUT2_10") (pintype "output"))
    )
    (net (code "40") (name "Net-(BORNIER_MOTEUR_DROITB-KL)") (class "Default")
      (node (ref "BORNIER_MOTEUR_DROIT") (pin "2") (pinfunction "KL_2") (pintype "passive"))
      (node (ref "MD-CBS1") (pin "2") (pinfunction "2_2") (pintype "passive"))
      (node (ref "MOTEUR_DROIT") (pin "2") (pinfunction "OUTPUT1_2") (pintype "output"))
    )
    (net (code "41") (name "Net-(BORNIER_MOTEUR_GAUCHEA-KL)") (class "Default")
      (node (ref "BORNIER_MOTEUR_GAUCHE") (pin "1") (pinfunction "KL_1") (pintype "passive"))
      (node (ref "MG-CBS2") (pin "2") (pinfunction "2_2") (pintype "passive"))
      (node (ref "MOTEUR_GAUCHE") (pin "10") (pinfunction "OUTPUT2_10") (pintype "output"))
    )
    (net (code "42") (name "Net-(BORNIER_MOTEUR_GAUCHEB-KL)") (class "Default")
      (node (ref "BORNIER_MOTEUR_GAUCHE") (pin "2") (pinfunction "KL_2") (pintype "passive"))
      (node (ref "MG-CBS1") (pin "2") (pinfunction "2_2") (pintype "passive"))
      (node (ref "MOTEUR_GAUCHE") (pin "2") (pinfunction "OUTPUT1_2") (pintype "output"))
    )
    (net (code "43") (name "Net-(BUZZERA-KL)") (class "Default")
      (node (ref "BUZZER") (pin "1") (pinfunction "KL_1") (pintype "passive"))
      (node (ref "LED1") (pin "A") (pinfunction "A_A") (pintype "passive"))
      (node (ref "R7") (pin "2") (pinfunction "2_2") (pintype "passive"))
      (node (ref "T2") (pin "C") (pinfunction "C_C") (pintype "passive"))
      (node (ref "T3") (pin "C") (pinfunction "C_C") (pintype "passive"))
      (node (ref "T4") (pin "C") (pinfunction "C_C") (pintype "passive"))
    )
    (net (code "44") (name "Net-(D1-PadA)") (class "Default")
      (node (ref "D1") (pin "A") (pinfunction "A_A") (pintype "passive"))
      (node (ref "R3") (pin "2") (pinfunction "2_2") (pintype "passive"))
      (node (ref "T1") (pin "B") (pinfunction "B_B") (pintype "passive"))
    )
    (net (code "45") (name "Net-(D1-PadC)") (class "Default")
      (node (ref "D1") (pin "C") (pinfunction "C_C") (pintype "passive"))
      (node (ref "D2") (pin "C") (pinfunction "C_C") (pintype "passive"))
      (node (ref "R1") (pin "1") (pinfunction "1_1") (pintype "passive"))
      (node (ref "R2") (pin "2") (pinfunction "2_2") (pintype "passive"))
    )
    (net (code "46") (name "Net-(D2-PadA)") (class "Default")
      (node (ref "D2") (pin "A") (pinfunction "A_A") (pintype "passive"))
      (node (ref "R5") (pin "2") (pinfunction "2_2") (pintype "passive"))
      (node (ref "T2") (pin "B") (pinfunction "B_B") (pintype "passive"))
    )
    (net (code "47") (name "Net-(D3-PadA)") (class "Default")
      (node (ref "D3") (pin "A") (pinfunction "A_A") (pintype "passive"))
      (node (ref "R6") (pin "2") (pinfunction "2_2") (pintype "passive"))
      (node (ref "T3") (pin "B") (pinfunction "B_B") (pintype "passive"))
    )
    (net (code "48") (name "Net-(D3-PadC)") (class "Default")
      (node (ref "D3") (pin "C") (pinfunction "C_C") (pintype "passive"))
      (node (ref "R2") (pin "1") (pinfunction "1_1") (pintype "passive"))
      (node (ref "R4") (pin "2") (pinfunction "2_2") (pintype "passive"))
    )
    (net (code "49") (name "Net-(D4-PadA)") (class "Default")
      (node (ref "D4") (pin "A") (pinfunction "A_A") (pintype "passive"))
      (node (ref "R8") (pin "2") (pinfunction "2_2") (pintype "passive"))
      (node (ref "T4") (pin "B") (pinfunction "B_B") (pintype "passive"))
    )
    (net (code "50") (name "Net-(D4-PadC)") (class "Default")
      (node (ref "D4") (pin "C") (pinfunction "C_C") (pintype "passive"))
      (node (ref "R4") (pin "1") (pinfunction "1_1") (pintype "passive"))
      (node (ref "R9") (pin "2") (pinfunction "2_2") (pintype "passive"))
    )
    (net (code "51") (name "Net-(DC1-VIN)") (class "Default")
      (node (ref "C2") (pin "+") (pinfunction "+_+") (pintype "passive"))
      (node (ref "DC1") (pin "1") (pinfunction "VIN_1") (pintype "passive"))
      (node (ref "L1") (pin "2") (pinfunction "2_2") (pintype "passive"))
    )
    (net (code "52") (name "Net-(DC2-VIN)") (class "Default")
      (node (ref "C4") (pin "+") (pinfunction "+_+") (pintype "passive"))
      (node (ref "DC2") (pin "1") (pinfunction "VIN_1") (pintype "passive"))
      (node (ref "L2") (pin "2") (pinfunction "2_2") (pintype "passive"))
    )
    (net (code "53") (name "Net-(DC3-VIN)") (class "Default")
      (node (ref "C10") (pin "+") (pinfunction "+_+") (pintype "passive"))
      (node (ref "DC3") (pin "1") (pinfunction "VIN_1") (pintype "passive"))
      (node (ref "L3") (pin "2") (pinfunction "2_2") (pintype "passive"))
    )
    (net (code "54") (name "Net-(DC3-VOUT)") (class "Default")
      (node (ref "DC3") (pin "3") (pinfunction "VOUT_3") (pintype "passive"))
      (node (ref "RASPBERRY") (pin "1") (pinfunction "1_1") (pintype "passive"))
    )
    (net (code "55") (name "Net-(K5A-1)") (class "Default")
      (node (ref "D5") (pin "A") (pinfunction "A_A") (pintype "passive"))
      (node (ref "K5") (pin "A1") (pinfunction "1_A1") (pintype "passive"))
      (node (ref "T1") (pin "C") (pinfunction "C_C") (pintype "passive"))
    )
    (net (code "56") (name "Net-(LED2-PadA)") (class "Default")
      (node (ref "LED2") (pin "A") (pinfunction "A_A") (pintype "passive"))
      (node (ref "T3") (pin "E") (pinfunction "E_E") (pintype "passive"))
    )
    (net (code "57") (name "Net-(LED3-PadA)") (class "Default")
      (node (ref "LED3") (pin "A") (pinfunction "A_A") (pintype "passive"))
      (node (ref "T4") (pin "E") (pinfunction "E_E") (pintype "passive"))
    )
    (net (code "58") (name "Net-(LED4-C)") (class "Default")
      (node (ref "LED4") (pin "K") (pinfunction "C_K") (pintype "passive"))
      (node (ref "R10") (pin "2") (pinfunction "2_2") (pintype "passive"))
    )
    (net (code "59") (name "Net-(MONTE-PLOT-BOOTSTRAP1)") (class "Default")
      (node (ref "MONTE-PLOT") (pin "1") (pinfunction "BOOTSTRAP1_1") (pintype "input"))
      (node (ref "MP-CBS1") (pin "1") (pinfunction "1_1") (pintype "passive"))
    )
    (net (code "60") (name "Net-(MONTE-PLOT-BOOTSTRAP2)") (class "Default")
      (node (ref "MONTE-PLOT") (pin "11") (pinfunction "BOOTSTRAP2_11") (pintype "input"))
      (node (ref "MP-CBS2") (pin "1") (pinfunction "1_1") (pintype "passive"))
    )
    (net (code "61") (name "Net-(MONTE-PLOT-DIRECTION)") (class "Default")
      (node (ref "MONTE-PLOT") (pin "3") (pinfunction "DIRECTION_3") (pintype "input"))
      (node (ref "MP-PU-DIR") (pin "2") (pinfunction "2_2") (pintype "passive"))
    )
    (net (code "62") (name "Net-(MONTE-PLOT-PWM)") (class "Default")
      (node (ref "MONTE-PLOT") (pin "5") (pinfunction "PWM_5") (pintype "input"))
      (node (ref "MP-PU-PWM") (pin "2") (pinfunction "2_2") (pintype "passive"))
    )
    (net (code "63") (name "Net-(MOTEUR_DROIT-BOOTSTRAP1)") (class "Default")
      (node (ref "MD-CBS1") (pin "1") (pinfunction "1_1") (pintype "passive"))
      (node (ref "MOTEUR_DROIT") (pin "1") (pinfunction "BOOTSTRAP1_1") (pintype "input"))
    )
    (net (code "64") (name "Net-(MOTEUR_DROIT-BOOTSTRAP2)") (class "Default")
      (node (ref "MD-CBS2") (pin "1") (pinfunction "1_1") (pintype "passive"))
      (node (ref "MOTEUR_DROIT") (pin "11") (pinfunction "BOOTSTRAP2_11") (pintype "input"))
    )
    (net (code "65") (name "Net-(MOTEUR_DROIT-DIRECTION)") (class "Default")
      (node (ref "MD-PU-DIR") (pin "2") (pinfunction "2_2") (pintype "passive"))
      (node (ref "MOTEUR_DROIT") (pin "3") (pinfunction "DIRECTION_3") (pintype "input"))
    )
    (net (code "66") (name "Net-(MOTEUR_DROIT-PWM)") (class "Default")
      (node (ref "MD-PU-PWM") (pin "2") (pinfunction "2_2") (pintype "passive"))
      (node (ref "MOTEUR_DROIT") (pin "5") (pinfunction "PWM_5") (pintype "input"))
    )
    (net (code "67") (name "Net-(MOTEUR_GAUCHE-BOOTSTRAP1)") (class "Default")
      (node (ref "MG-CBS1") (pin "1") (pinfunction "1_1") (pintype "passive"))
      (node (ref "MOTEUR_GAUCHE") (pin "1") (pinfunction "BOOTSTRAP1_1") (pintype "input"))
    )
    (net (code "68") (name "Net-(MOTEUR_GAUCHE-BOOTSTRAP2)") (class "Default")
      (node (ref "MG-CBS2") (pin "1") (pinfunction "1_1") (pintype "passive"))
      (node (ref "MOTEUR_GAUCHE") (pin "11") (pinfunction "BOOTSTRAP2_11") (pintype "input"))
    )
    (net (code "69") (name "Net-(MOTEUR_GAUCHE-DIRECTION)") (class "Default")
      (node (ref "MG-PU-DIR") (pin "2") (pinfunction "2_2") (pintype "passive"))
      (node (ref "MOTEUR_GAUCHE") (pin "3") (pinfunction "DIRECTION_3") (pintype "input"))
    )
    (net (code "70") (name "Net-(MOTEUR_GAUCHE-PWM)") (class "Default")
      (node (ref "MG-PU-PWM") (pin "2") (pinfunction "2_2") (pintype "passive"))
      (node (ref "MOTEUR_GAUCHE") (pin "5") (pinfunction "PWM_5") (pintype "input"))
    )
    (net (code "71") (name "unconnected-(K5B-O-Pad12)") (class "Default")
      (node (ref "K5") (pin "12") (pinfunction "O_12") (pintype "passive"))
    )
    (net (code "72") (name "unconnected-(MONTE-PLOT-SENSE-Pad8)") (class "Default")
      (node (ref "MONTE-PLOT") (pin "8") (pinfunction "SENSE_8") (pintype "output"))
    )
    (net (code "73") (name "unconnected-(MONTE-PLOT-THERMAL-Pad9)") (class "Default")
      (node (ref "MONTE-PLOT") (pin "9") (pinfunction "THERMAL_9") (pintype "output"))
    )
    (net (code "74") (name "unconnected-(MOTEUR_DROIT-SENSE-Pad8)") (class "Default")
      (node (ref "MOTEUR_DROIT") (pin "8") (pinfunction "SENSE_8") (pintype "output"))
    )
    (net (code "75") (name "unconnected-(MOTEUR_DROIT-THERMAL-Pad9)") (class "Default")
      (node (ref "MOTEUR_DROIT") (pin "9") (pinfunction "THERMAL_9") (pintype "output"))
    )
    (net (code "76") (name "unconnected-(MOTEUR_GAUCHE-SENSE-Pad8)") (class "Default")
      (node (ref "MOTEUR_GAUCHE") (pin "8") (pinfunction "SENSE_8") (pintype "output"))
    )
    (net (code "77") (name "unconnected-(MOTEUR_GAUCHE-THERMAL-Pad9)") (class "Default")
      (node (ref "MOTEUR_GAUCHE") (pin "9") (pinfunction "THERMAL_9") (pintype "output"))
    )
    (net (code "78") (name "unconnected-(RASPBERRY-Pad2)") (class "Default")
      (node (ref "RASPBERRY") (pin "2") (pinfunction "2_2") (pintype "passive"))
    )
    (net (code "79") (name "unconnected-(RASPBERRY-Pad3)") (class "Default")
      (node (ref "RASPBERRY") (pin "3") (pinfunction "3_3") (pintype "passive"))
    )
    (net (code "80") (name "unconnected-(U$1-BOOT0-PadP$71)") (class "Default")
      (node (ref "U$1") (pin "P$71") (pinfunction "BOOT0_P$71") (pintype "bidirectional"))
    )
    (net (code "81") (name "unconnected-(U$1-GND8-PadP$99)") (class "Default")
      (node (ref "U$1") (pin "P$99") (pinfunction "GND8_P$99") (pintype "bidirectional"))
    )
    (net (code "82") (name "unconnected-(U$1-NC-PadP$48)") (class "Default")
      (node (ref "U$1") (pin "P$48") (pinfunction "NC_P$48") (pintype "bidirectional"))
    )
    (net (code "83") (name "unconnected-(U$1-NRST-PadP$6)") (class "Default")
      (node (ref "U$1") (pin "P$6") (pinfunction "NRST_P$6") (pintype "bidirectional"))
    )
    (net (code "84") (name "unconnected-(U$1-PA8-PadP$93)") (class "Default")
      (node (ref "U$1") (pin "P$93") (pinfunction "PA8_P$93") (pintype "bidirectional"))
    )
    (net (code "85") (name "unconnected-(U$1-PA9-PadP$94)") (class "Default")
      (node (ref "U$1") (pin "P$94") (pinfunction "PA9_P$94") (pintype "bidirectional"))
    )
    (net (code "86") (name "unconnected-(U$1-PA14-PadP$89)") (class "Default")
      (node (ref "U$1") (pin "P$89") (pinfunction "PA14_P$89") (pintype "bidirectional"))
    )
    (net (code "87") (name "unconnected-(U$1-PA15-PadP$90)") (class "Default")
      (node (ref "U$1") (pin "P$90") (pinfunction "PA15_P$90") (pintype "bidirectional"))
    )
    (net (code "88") (name "unconnected-(U$1-PB0-PadP$22)") (class "Default")
      (node (ref "U$1") (pin "P$22") (pinfunction "PB0_P$22") (pintype "bidirectional"))
    )
    (net (code "89") (name "unconnected-(U$1-PB3-PadP$78)") (class "Default")
      (node (ref "U$1") (pin "P$78") (pinfunction "PB3_P$78") (pintype "bidirectional"))
    )
    (net (code "90") (name "unconnected-(U$1-PB8-PadP$69)") (class "Default")
      (node (ref "U$1") (pin "P$69") (pinfunction "PB8_P$69") (pintype "bidirectional"))
    )
    (net (code "91") (name "unconnected-(U$1-PB9-PadP$70)") (class "Default")
      (node (ref "U$1") (pin "P$70") (pinfunction "PB9_P$70") (pintype "bidirectional"))
    )
    (net (code "92") (name "unconnected-(U$1-PB10-PadP$34)") (class "Default")
      (node (ref "U$1") (pin "P$34") (pinfunction "PB10_P$34") (pintype "bidirectional"))
    )
    (net (code "93") (name "unconnected-(U$1-PB11-PadP$35)") (class "Default")
      (node (ref "U$1") (pin "P$35") (pinfunction "PB11_P$35") (pintype "bidirectional"))
    )
    (net (code "94") (name "unconnected-(U$1-PB12-PadP$36)") (class "Default")
      (node (ref "U$1") (pin "P$36") (pinfunction "PB12_P$36") (pintype "bidirectional"))
    )
    (net (code "95") (name "unconnected-(U$1-PB13-PadP$37)") (class "Default")
      (node (ref "U$1") (pin "P$37") (pinfunction "PB13_P$37") (pintype "bidirectional"))
    )
    (net (code "96") (name "unconnected-(U$1-PB14-PadP$38)") (class "Default")
      (node (ref "U$1") (pin "P$38") (pinfunction "PB14_P$38") (pintype "bidirectional"))
    )
    (net (code "97") (name "unconnected-(U$1-PB15-PadP$39)") (class "Default")
      (node (ref "U$1") (pin "P$39") (pinfunction "PB15_P$39") (pintype "bidirectional"))
    )
    (net (code "98") (name "unconnected-(U$1-PC0-PadP$8)") (class "Default")
      (node (ref "U$1") (pin "P$8") (pinfunction "PC0_P$8") (pintype "bidirectional"))
    )
    (net (code "99") (name "unconnected-(U$1-PC1-PadP$7)") (class "Default")
      (node (ref "U$1") (pin "P$7") (pinfunction "PC1_P$7") (pintype "bidirectional"))
    )
    (net (code "100") (name "unconnected-(U$1-PC2-PadP$10)") (class "Default")
      (node (ref "U$1") (pin "P$10") (pinfunction "PC2_P$10") (pintype "bidirectional"))
    )
    (net (code "101") (name "unconnected-(U$1-PC3-PadP$9)") (class "Default")
      (node (ref "U$1") (pin "P$9") (pinfunction "PC3_P$9") (pintype "bidirectional"))
    )
    (net (code "102") (name "unconnected-(U$1-PC4-PadP$20)") (class "Default")
      (node (ref "U$1") (pin "P$20") (pinfunction "PC4_P$20") (pintype "bidirectional"))
    )
    (net (code "103") (name "unconnected-(U$1-PC10-PadP$87)") (class "Default")
      (node (ref "U$1") (pin "P$87") (pinfunction "PC10_P$87") (pintype "bidirectional"))
    )
    (net (code "104") (name "unconnected-(U$1-PC12-PadP$85)") (class "Default")
      (node (ref "U$1") (pin "P$85") (pinfunction "PC12_P$85") (pintype "bidirectional"))
    )
    (net (code "105") (name "unconnected-(U$1-PC14-PadP$59)") (class "Default")
      (node (ref "U$1") (pin "P$59") (pinfunction "PC14_P$59") (pintype "bidirectional"))
    )
    (net (code "106") (name "unconnected-(U$1-PD1-PadP$83)") (class "Default")
      (node (ref "U$1") (pin "P$83") (pinfunction "PD1_P$83") (pintype "bidirectional"))
    )
    (net (code "107") (name "unconnected-(U$1-PD3-PadP$81)") (class "Default")
      (node (ref "U$1") (pin "P$81") (pinfunction "PD3_P$81") (pintype "bidirectional"))
    )
    (net (code "108") (name "unconnected-(U$1-PD4-PadP$82)") (class "Default")
      (node (ref "U$1") (pin "P$82") (pinfunction "PD4_P$82") (pintype "bidirectional"))
    )
    (net (code "109") (name "unconnected-(U$1-PD5-PadP$79)") (class "Default")
      (node (ref "U$1") (pin "P$79") (pinfunction "PD5_P$79") (pintype "bidirectional"))
    )
    (net (code "110") (name "unconnected-(U$1-PD7-PadP$77)") (class "Default")
      (node (ref "U$1") (pin "P$77") (pinfunction "PD7_P$77") (pintype "bidirectional"))
    )
    (net (code "111") (name "unconnected-(U$1-PD8-PadP$40)") (class "Default")
      (node (ref "U$1") (pin "P$40") (pinfunction "PD8_P$40") (pintype "bidirectional"))
    )
    (net (code "112") (name "unconnected-(U$1-PD13-PadP$45)") (class "Default")
      (node (ref "U$1") (pin "P$45") (pinfunction "PD13_P$45") (pintype "bidirectional"))
    )
    (net (code "113") (name "unconnected-(U$1-PD15-PadP$47)") (class "Default")
      (node (ref "U$1") (pin "P$47") (pinfunction "PD15_P$47") (pintype "bidirectional"))
    )
    (net (code "114") (name "unconnected-(U$1-PE0-PadP$67)") (class "Default")
      (node (ref "U$1") (pin "P$67") (pinfunction "PE0_P$67") (pintype "bidirectional"))
    )
    (net (code "115") (name "unconnected-(U$1-PE1-PadP$68)") (class "Default")
      (node (ref "U$1") (pin "P$68") (pinfunction "PE1_P$68") (pintype "bidirectional"))
    )
    (net (code "116") (name "unconnected-(U$1-PE4-PadP$63)") (class "Default")
      (node (ref "U$1") (pin "P$63") (pinfunction "PE4_P$63") (pintype "bidirectional"))
    )
    (net (code "117") (name "unconnected-(U$1-PE6-PadP$61)") (class "Default")
      (node (ref "U$1") (pin "P$61") (pinfunction "PE6_P$61") (pintype "bidirectional"))
    )
    (net (code "118") (name "unconnected-(U$1-PE7-PadP$25)") (class "Default")
      (node (ref "U$1") (pin "P$25") (pinfunction "PE7_P$25") (pintype "bidirectional"))
    )
    (net (code "119") (name "unconnected-(U$1-PE8-PadP$26)") (class "Default")
      (node (ref "U$1") (pin "P$26") (pinfunction "PE8_P$26") (pintype "bidirectional"))
    )
    (net (code "120") (name "unconnected-(U$1-PE9-PadP$27)") (class "Default")
      (node (ref "U$1") (pin "P$27") (pinfunction "PE9_P$27") (pintype "bidirectional"))
    )
    (net (code "121") (name "unconnected-(U$1-PE10-PadP$28)") (class "Default")
      (node (ref "U$1") (pin "P$28") (pinfunction "PE10_P$28") (pintype "bidirectional"))
    )
    (net (code "122") (name "unconnected-(U$1-PE11-PadP$29)") (class "Default")
      (node (ref "U$1") (pin "P$29") (pinfunction "PE11_P$29") (pintype "bidirectional"))
    )
    (net (code "123") (name "unconnected-(U$1-PE12-PadP$30)") (class "Default")
      (node (ref "U$1") (pin "P$30") (pinfunction "PE12_P$30") (pintype "bidirectional"))
    )
    (net (code "124") (name "unconnected-(U$1-PE13-PadP$31)") (class "Default")
      (node (ref "U$1") (pin "P$31") (pinfunction "PE13_P$31") (pintype "bidirectional"))
    )
    (net (code "125") (name "unconnected-(U$1-PE14-PadP$32)") (class "Default")
      (node (ref "U$1") (pin "P$32") (pinfunction "PE14_P$32") (pintype "bidirectional"))
    )
    (net (code "126") (name "unconnected-(U$1-PE15-PadP$33)") (class "Default")
      (node (ref "U$1") (pin "P$33") (pinfunction "PE15_P$33") (pintype "bidirectional"))
    )
    (net (code "127") (name "unconnected-(U$1-PH0-PadP$57)") (class "Default")
      (node (ref "U$1") (pin "P$57") (pinfunction "PH0_P$57") (pintype "bidirectional"))
    )
    (net (code "128") (name "unconnected-(U$1-PH1-PadP$58)") (class "Default")
      (node (ref "U$1") (pin "P$58") (pinfunction "PH1_P$58") (pintype "bidirectional"))
    )
    (net (code "129") (name "unconnected-(U$1-VDD-PadP$3)") (class "Default")
      (node (ref "U$1") (pin "P$3") (pinfunction "VDD_P$3") (pintype "bidirectional"))
    )
    (net (code "130") (name "unconnected-(U$1-VDD1-PadP$4)") (class "Default")
      (node (ref "U$1") (pin "P$4") (pinfunction "VDD1_P$4") (pintype "bidirectional"))
    )
    (net (code "131") (name "unconnected-(U$1-VDD2-PadP$55)") (class "Default")
      (node (ref "U$1") (pin "P$55") (pinfunction "VDD2_P$55") (pintype "bidirectional"))
    )
    (net (code "132") (name "unconnected-(U$1-VDD3-PadP$56)") (class "Default")
      (node (ref "U$1") (pin "P$56") (pinfunction "VDD3_P$56") (pintype "bidirectional"))
    )
    (net (code "133") (name "unconnected-(U$1-VDD4-PadP$72)") (class "Default")
      (node (ref "U$1") (pin "P$72") (pinfunction "VDD4_P$72") (pintype "bidirectional"))
    )
  )
)
